# 2017-08-24_19-39-041.net
KiCad netlist of a schematic drawn in Altium Designer
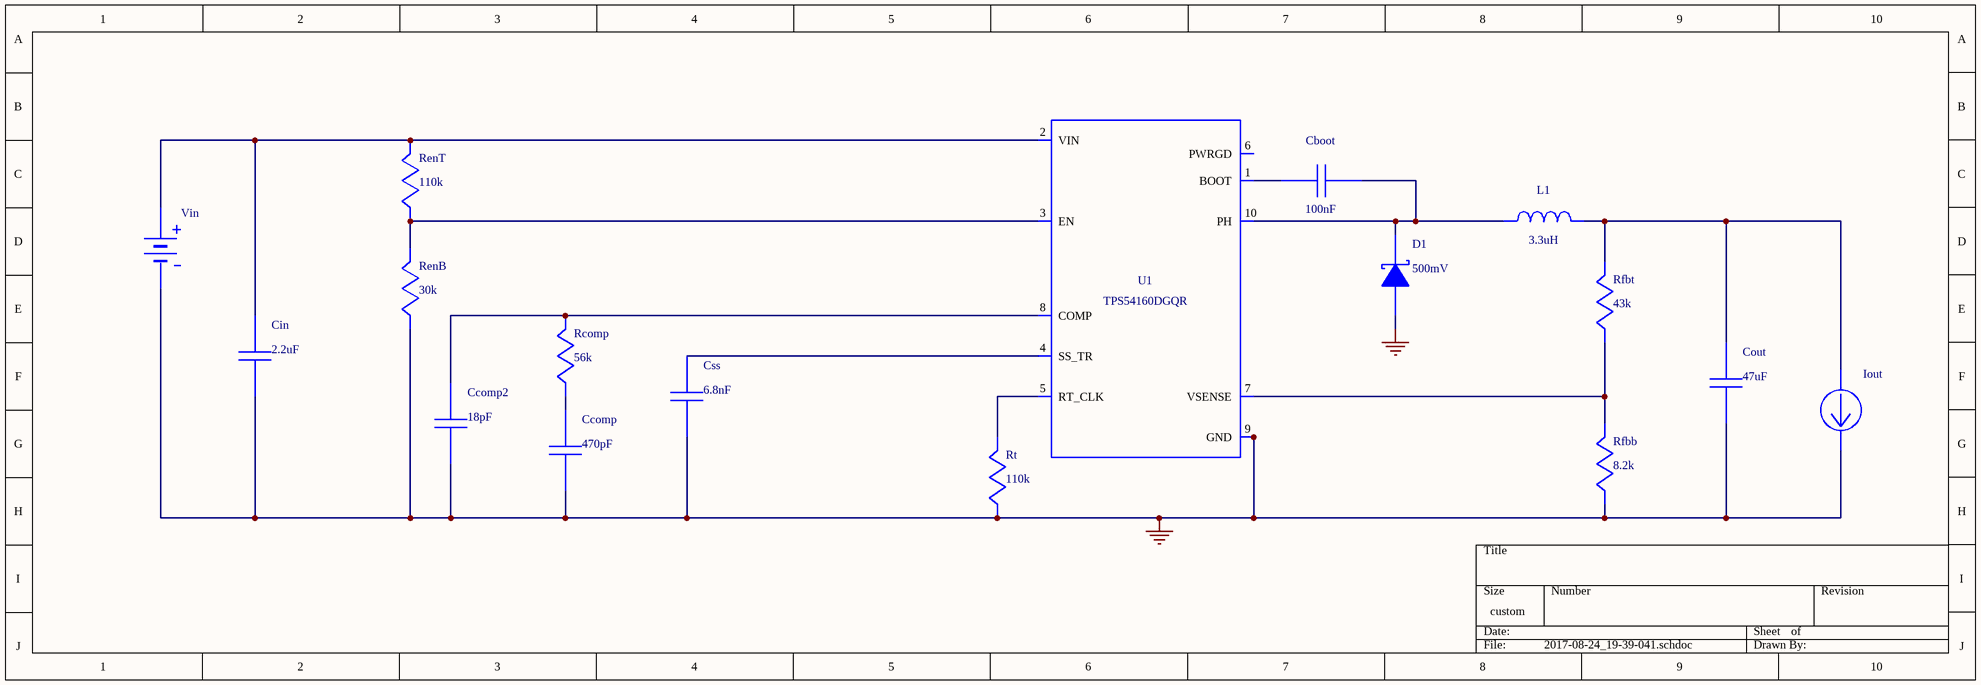
[diagram p0: 2017-08-24_19-39-041.schdoc]

(export (version "E")
  (design (tool "Eeschema 10.0.6"))
  (components
    (comp (ref "Cboot")
      (value "100nF")
      (description "GRM155R61A104KA0")
      (fields (field (name "MANUFACTURER PART NUMBER") "GRM155R61A104KA01D"))
      (libsource (lib "TI WEBENCH") (part "Cboot"))
    )
    (comp (ref "Ccomp")
      (value "470pF")
      (description "CC0805KRX7R9BB47")
      (fields (field (name "MANUFACTURER PART NUMBER") "CC0805KRX7R9BB471"))
      (libsource (lib "TI WEBENCH") (part "Ccomp"))
    )
    (comp (ref "Ccomp2")
      (value "18pF")
      (footprint "RAD-0.1")
      (description "C0805C180K5GACTU")
      (libsource (lib "TI WEBENCH") (part "Ccomp2"))
    )
    (comp (ref "Cin")
      (value "2.2uF")
      (description "GRM188R61A225KE3")
      (fields (field (name "MANUFACTURER PART NUMBER") "GRM188R61A225KE34D"))
      (libsource (lib "TI WEBENCH") (part "Cin"))
    )
    (comp (ref "Cout")
      (value "47uF")
      (description "C2012X5R1A476M12")
      (fields (field (name "MANUFACTURER PART NUMBER") "C2012X5R1A476M125AC"))
      (libsource (lib "TI WEBENCH") (part "Cout"))
    )
    (comp (ref "Css")
      (value "6.8nF")
      (description "CC0805KRX7R9BB68")
      (fields (field (name "MANUFACTURER PART NUMBER") "CC0805KRX7R9BB682"))
      (libsource (lib "TI WEBENCH") (part "Css"))
    )
    (comp (ref "D1") (value "500mV") (description "B340A-13-F") (libsource (lib "TI WEBENCH") (part "D1")))
    (comp (ref "Iout") (value "WB_CURRENT_LOAD") (libsource (lib "TI WEBENCH") (part "Iout")))
    (comp (ref "L1") (value "3.3uH") (description "SRN6045-3R3Y") (libsource (lib "TI WEBENCH") (part "L1")))
    (comp (ref "Rcomp")
      (value "56k")
      (footprint "AXIAL-0.4")
      (description "RC1206FR-0756KL")
      (libsource (lib "TI WEBENCH") (part "Rcomp"))
    )
    (comp (ref "RenB")
      (value "30k")
      (footprint "AXIAL-0.4")
      (description "RC1206FR-0730KL")
      (libsource (lib "TI WEBENCH") (part "RenB"))
    )
    (comp (ref "RenT")
      (value "110k")
      (footprint "AXIAL-0.4")
      (description "ERJ-8ENF1103V")
      (libsource (lib "TI WEBENCH") (part "RenT"))
    )
    (comp (ref "Rfbb")
      (value "8.2k")
      (footprint "AXIAL-0.4")
      (description "RC1206FR-078K2L")
      (libsource (lib "TI WEBENCH") (part "Rfbb"))
    )
    (comp (ref "Rfbt")
      (value "43k")
      (footprint "AXIAL-0.4")
      (description "RC1206FR-0743KL")
      (libsource (lib "TI WEBENCH") (part "Rfbt"))
    )
    (comp (ref "Rt")
      (value "110k")
      (footprint "AXIAL-0.4")
      (description "CRCW1206110KFKEA")
      (libsource (lib "TI WEBENCH") (part "Rt"))
    )
    (comp (ref "U1")
      (value "TPS54140DGQR")
      (footprint "Miscellaneous Devices:N10A")
      (description "TPS54160DGQR")
      (fields (field (name "PACKAGEREFERENCE") "TPS54160DGQR"))
      (libsource (lib "TI WEBENCH") (part "U1"))
    )
    (comp (ref "Vin") (value "WB_BATTERY") (libsource (lib "TI WEBENCH") (part "Vin")))
  )
  (nets
    (net (code "1") (name "0") (class "Default")
      (node (ref "Ccomp") (pin "2") (pinfunction "2_2") (pintype "passive"))
      (node (ref "Ccomp2") (pin "2") (pinfunction "2_2") (pintype "passive"))
      (node (ref "Cin") (pin "2") (pinfunction "2_2") (pintype "passive"))
      (node (ref "Cout") (pin "2") (pinfunction "2_2") (pintype "passive"))
      (node (ref "Css") (pin "2") (pinfunction "2_2") (pintype "passive"))
      (node (ref "D1") (pin "2") (pinfunction "A_2") (pintype "passive"))
      (node (ref "Iout") (pin "2") (pinfunction "-_2") (pintype "passive"))
      (node (ref "RenB") (pin "2") (pinfunction "2_2") (pintype "passive"))
      (node (ref "Rfbb") (pin "2") (pinfunction "2_2") (pintype "passive"))
      (node (ref "Rt") (pin "2") (pinfunction "2_2") (pintype "passive"))
      (node (ref "U1") (pin "11") (pinfunction "EPAD_11") (pintype "passive"))
      (node (ref "U1") (pin "9") (pinfunction "GND_9") (pintype "passive"))
      (node (ref "Vin") (pin "2") (pinfunction "-_2") (pintype "passive"))
    )
    (net (code "2") (name "Net-(Ccomp-Pad1)") (class "Default")
      (node (ref "Ccomp") (pin "1") (pinfunction "1_1") (pintype "passive"))
      (node (ref "Rcomp") (pin "2") (pinfunction "2_2") (pintype "passive"))
    )
    (net (code "3") (name "Net-(D1-K)") (class "Default")
      (node (ref "Cboot") (pin "2") (pinfunction "2_2") (pintype "passive"))
      (node (ref "D1") (pin "1") (pinfunction "K_1") (pintype "passive"))
      (node (ref "L1") (pin "2") (pinfunction "2_2") (pintype "passive"))
      (node (ref "U1") (pin "10") (pinfunction "PH_10") (pintype "passive"))
    )
    (net (code "4") (name "Net-(Iout-+)") (class "Default")
      (node (ref "Cout") (pin "1") (pinfunction "1_1") (pintype "passive"))
      (node (ref "Iout") (pin "1") (pinfunction "+_1") (pintype "passive"))
      (node (ref "L1") (pin "1") (pinfunction "1_1") (pintype "passive"))
      (node (ref "Rfbt") (pin "1") (pinfunction "1_1") (pintype "passive"))
    )
    (net (code "5") (name "Net-(U1-BOOT)") (class "Default")
      (node (ref "Cboot") (pin "1") (pinfunction "1_1") (pintype "passive"))
      (node (ref "U1") (pin "1") (pinfunction "BOOT_1") (pintype "passive"))
    )
    (net (code "6") (name "Net-(U1-COMP)") (class "Default")
      (node (ref "Ccomp2") (pin "1") (pinfunction "1_1") (pintype "passive"))
      (node (ref "Rcomp") (pin "1") (pinfunction "1_1") (pintype "passive"))
      (node (ref "U1") (pin "8") (pinfunction "COMP_8") (pintype "passive"))
    )
    (net (code "7") (name "Net-(U1-EN)") (class "Default")
      (node (ref "RenB") (pin "1") (pinfunction "1_1") (pintype "passive"))
      (node (ref "RenT") (pin "2") (pinfunction "2_2") (pintype "passive"))
      (node (ref "U1") (pin "3") (pinfunction "EN_3") (pintype "passive"))
    )
    (net (code "8") (name "Net-(U1-RT_CLK)") (class "Default")
      (node (ref "Rt") (pin "1") (pinfunction "1_1") (pintype "passive"))
      (node (ref "U1") (pin "5") (pinfunction "RT_CLK_5") (pintype "passive"))
    )
    (net (code "9") (name "Net-(U1-SS_TR)") (class "Default")
      (node (ref "Css") (pin "1") (pinfunction "1_1") (pintype "passive"))
      (node (ref "U1") (pin "4") (pinfunction "SS_TR_4") (pintype "passive"))
    )
    (net (code "10") (name "Net-(U1-VIN)") (class "Default")
      (node (ref "Cin") (pin "1") (pinfunction "1_1") (pintype "passive"))
      (node (ref "RenT") (pin "1") (pinfunction "1_1") (pintype "passive"))
      (node (ref "U1") (pin "2") (pinfunction "VIN_2") (pintype "passive"))
      (node (ref "Vin") (pin "1") (pinfunction "+_1") (pintype "passive"))
    )
    (net (code "11") (name "Net-(U1-VSENSE)") (class "Default")
      (node (ref "Rfbb") (pin "1") (pinfunction "1_1") (pintype "passive"))
      (node (ref "Rfbt") (pin "2") (pinfunction "2_2") (pintype "passive"))
      (node (ref "U1") (pin "7") (pinfunction "VSENSE_7") (pintype "passive"))
    )
    (net (code "12") (name "unconnected-(U1-PWRGD-Pad6)") (class "Default")
      (node (ref "U1") (pin "6") (pinfunction "PWRGD_6") (pintype "passive"))
    )
  )
)
